# Sheet_1.net
KiCad netlist of a schematic drawn in Altium Designer
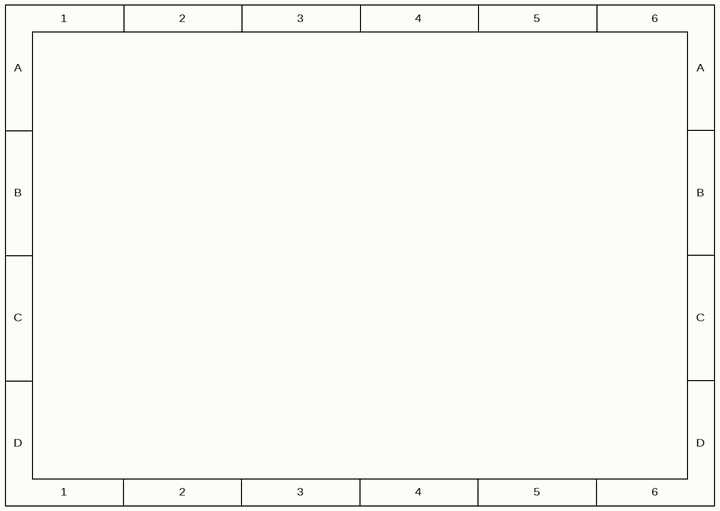
[diagram p0: Sheet_1.schdoc]

(export (version "E")
  (design (tool "Eeschema 10.0.6"))
  (components
    (comp (ref "JP5")
      (value "M02PTH")
      (description "Header 2")
      (fields (field (name "BOM_MANUFACTURER PART") "?"))
      (libsource (lib "altium-import") (part "root_0_M02PTH_"))
    )
    (comp (ref "MOTORS")
      (value "4 HEADER")
      (description "4 Pin Header")
      (fields (field (name "BOM_MANUFACTURER PART") "?"))
      (libsource (lib "altium-import") (part "root_1_4 HEADER_"))
    )
    (comp (ref "SERVO1")
      (value "M031X03_NO_SILK")
      (description "Header 3")
      (fields (field (name "BOM_MANUFACTURER PART") "?") (field (name "CONTRIBUTOR") "SparkFun"))
      (libsource (lib "altium-import") (part "root_0_M031X03_NO_SILK_"))
    )
    (comp (ref "SERVO2")
      (value "M031X03_NO_SILK")
      (description "Header 3")
      (fields (field (name "BOM_MANUFACTURER PART") "?") (field (name "CONTRIBUTOR") "SparkFun"))
      (libsource (lib "altium-import") (part "root_0_M031X03_NO_SILK_"))
    )
    (comp (ref "U1")
      (value "Node")
      (fields (field (name "BOM_MANUFACTURER PART") "NodeMcu V3 LoLin") (field (name "CONTRIBUTOR") "nitink"))
      (libsource (lib "altium-import") (part "root_0_Node_"))
    )
    (comp (ref "U2")
      (value "TB6612")
      (fields (field (name "BOM_MANUFACTURER PART") "?"))
      (libsource (lib "altium-import") (part "root_3_TB6612_"))
    )
  )
  (nets
    (net (code "1") (name "Net-(JP5-Pad2)") (class "Default")
      (node (ref "JP5") (pin "2") (pinfunction "2_2") (pintype "passive"))
      (node (ref "U1") (pin "10") (pinfunction "GND_10") (pintype "passive"))
    )
    (net (code "2") (name "Net-(SERVO1-Pad1)") (class "Default")
      (node (ref "SERVO1") (pin "1") (pinfunction "1_1") (pintype "passive"))
      (node (ref "SERVO2") (pin "1") (pinfunction "1_1") (pintype "passive"))
      (node (ref "U1") (pin "17") (pinfunction "GND_17") (pintype "passive"))
    )
    (net (code "3") (name "Net-(U1-D0)") (class "Default")
      (node (ref "U1") (pin "30") (pinfunction "D0_30") (pintype "passive"))
      (node (ref "U2") (pin "15") (pinfunction "AIN2_15") (pintype "passive"))
    )
    (net (code "4") (name "Net-(U1-D1)") (class "Default")
      (node (ref "U1") (pin "29") (pinfunction "D1_29") (pintype "passive"))
      (node (ref "U2") (pin "12") (pinfunction "BIN1_12") (pintype "passive"))
    )
    (net (code "5") (name "Net-(U1-D2)") (class "Default")
      (node (ref "U1") (pin "28") (pinfunction "D2_28") (pintype "passive"))
      (node (ref "U2") (pin "10") (pinfunction "PWMB_10") (pintype "passive"))
    )
    (net (code "6") (name "Net-(U1-D3)") (class "Default")
      (node (ref "U1") (pin "27") (pinfunction "D3_27") (pintype "passive"))
      (node (ref "U2") (pin "14") (pinfunction "AIN1_14") (pintype "passive"))
    )
    (net (code "7") (name "Net-(U1-D5)") (class "Default")
      (node (ref "U1") (pin "23") (pinfunction "D5_23") (pintype "passive"))
      (node (ref "U2") (pin "11") (pinfunction "BIN2_11") (pintype "passive"))
    )
    (net (code "8") (name "Net-(U1-D6)") (class "Default")
      (node (ref "U1") (pin "22") (pinfunction "D6_22") (pintype "passive"))
      (node (ref "U2") (pin "16") (pinfunction "PWMA_16") (pintype "passive"))
    )
    (net (code "9") (name "Net-(U1-D7)") (class "Default")
      (node (ref "SERVO2") (pin "3") (pinfunction "3_3") (pintype "passive"))
      (node (ref "U1") (pin "21") (pinfunction "D7_21") (pintype "passive"))
    )
    (net (code "10") (name "Net-(U1-D8)") (class "Default")
      (node (ref "SERVO1") (pin "3") (pinfunction "3_3") (pintype "passive"))
      (node (ref "U1") (pin "20") (pinfunction "D8_20") (pintype "passive"))
    )
    (net (code "11") (name "Net-(U1-GND-Pad24)") (class "Default")
      (node (ref "U1") (pin "24") (pinfunction "GND_24") (pintype "passive"))
      (node (ref "U2") (pin "8") (pinfunction "GND_8") (pintype "passive"))
    )
    (net (code "12") (name "Net-(U1-Vin)") (class "Default")
      (node (ref "JP5") (pin "1") (pinfunction "1_1") (pintype "passive"))
      (node (ref "SERVO1") (pin "2") (pinfunction "2_2") (pintype "passive"))
      (node (ref "SERVO2") (pin "2") (pinfunction "2_2") (pintype "passive"))
      (node (ref "U1") (pin "15") (pinfunction "Vin_15") (pintype "passive"))
      (node (ref "U2") (pin "1") (pinfunction "VM_1") (pintype "passive"))
    )
    (net (code "13") (name "Net-(U2-A01)") (class "Default")
      (node (ref "MOTORS") (pin "4") (pinfunction "4_4") (pintype "passive"))
      (node (ref "U2") (pin "4") (pinfunction "A01_4") (pintype "passive"))
    )
    (net (code "14") (name "Net-(U2-A02)") (class "Default")
      (node (ref "MOTORS") (pin "3") (pinfunction "3_3") (pintype "passive"))
      (node (ref "U2") (pin "5") (pinfunction "A02_5") (pintype "passive"))
    )
    (net (code "15") (name "Net-(U2-B01)") (class "Default")
      (node (ref "MOTORS") (pin "1") (pinfunction "1_1") (pintype "passive"))
      (node (ref "U2") (pin "7") (pinfunction "B01_7") (pintype "passive"))
    )
    (net (code "16") (name "Net-(U2-B02)") (class "Default")
      (node (ref "MOTORS") (pin "2") (pinfunction "2_2") (pintype "passive"))
      (node (ref "U2") (pin "6") (pinfunction "B02_6") (pintype "passive"))
    )
    (net (code "17") (name "Net-(U2-STBY)") (class "Default")
      (node (ref "U1") (pin "25") (pinfunction "3.3V_25") (pintype "passive"))
      (node (ref "U2") (pin "13") (pinfunction "STBY_13") (pintype "passive"))
      (node (ref "U2") (pin "2") (pinfunction "VCC_2") (pintype "passive"))
    )
    (net (code "18") (name "unconnected-(U1-3.3V-Pad11)") (class "Default")
      (node (ref "U1") (pin "11") (pinfunction "3.3V_11") (pintype "passive"))
    )
    (net (code "19") (name "unconnected-(U1-3.3V-Pad16)") (class "Default")
      (node (ref "U1") (pin "16") (pinfunction "3.3V_16") (pintype "passive"))
    )
    (net (code "20") (name "unconnected-(U1-A0-Pad1)") (class "Default")
      (node (ref "U1") (pin "1") (pinfunction "A0_1") (pintype "passive"))
    )
    (net (code "21") (name "unconnected-(U1-D4-Pad26)") (class "Default")
      (node (ref "U1") (pin "26") (pinfunction "D4_26") (pintype "passive"))
    )
    (net (code "22") (name "unconnected-(U1-EN-Pad12)") (class "Default")
      (node (ref "U1") (pin "12") (pinfunction "EN_12") (pintype "passive"))
    )
    (net (code "23") (name "unconnected-(U1-GND-Pad2)") (class "Default")
      (node (ref "U1") (pin "2") (pinfunction "GND_2") (pintype "passive"))
    )
    (net (code "24") (name "unconnected-(U1-GND-Pad14)") (class "Default")
      (node (ref "U1") (pin "14") (pinfunction "GND_14") (pintype "passive"))
    )
    (net (code "25") (name "unconnected-(U1-RST-Pad13)") (class "Default")
      (node (ref "U1") (pin "13") (pinfunction "RST_13") (pintype "passive"))
    )
    (net (code "26") (name "unconnected-(U1-RX-Pad19)") (class "Default")
      (node (ref "U1") (pin "19") (pinfunction "RX_19") (pintype "passive"))
    )
    (net (code "27") (name "unconnected-(U1-S0-Pad8)") (class "Default")
      (node (ref "U1") (pin "8") (pinfunction "S0_8") (pintype "passive"))
    )
    (net (code "28") (name "unconnected-(U1-S1-Pad6)") (class "Default")
      (node (ref "U1") (pin "6") (pinfunction "S1_6") (pintype "passive"))
    )
    (net (code "29") (name "unconnected-(U1-S2-Pad5)") (class "Default")
      (node (ref "U1") (pin "5") (pinfunction "S2_5") (pintype "passive"))
    )
    (net (code "30") (name "unconnected-(U1-S3-Pad4)") (class "Default")
      (node (ref "U1") (pin "4") (pinfunction "S3_4") (pintype "passive"))
    )
    (net (code "31") (name "unconnected-(U1-SC-Pad7)") (class "Default")
      (node (ref "U1") (pin "7") (pinfunction "SC_7") (pintype "passive"))
    )
    (net (code "32") (name "unconnected-(U1-SK-Pad9)") (class "Default")
      (node (ref "U1") (pin "9") (pinfunction "SK_9") (pintype "passive"))
    )
    (net (code "33") (name "unconnected-(U1-TX-Pad18)") (class "Default")
      (node (ref "U1") (pin "18") (pinfunction "TX_18") (pintype "passive"))
    )
    (net (code "34") (name "unconnected-(U1-VU-Pad3)") (class "Default")
      (node (ref "U1") (pin "3") (pinfunction "VU_3") (pintype "passive"))
    )
    (net (code "35") (name "unconnected-(U2-GND-Pad3)") (class "Default")
      (node (ref "U2") (pin "3") (pinfunction "GND_3") (pintype "passive"))
    )
    (net (code "36") (name "unconnected-(U2-GND-Pad9)") (class "Default")
      (node (ref "U2") (pin "9") (pinfunction "GND_9") (pintype "passive"))
    )
  )
)
